# detectino.net
KiCad netlist of a schematic drawn in EAGLE
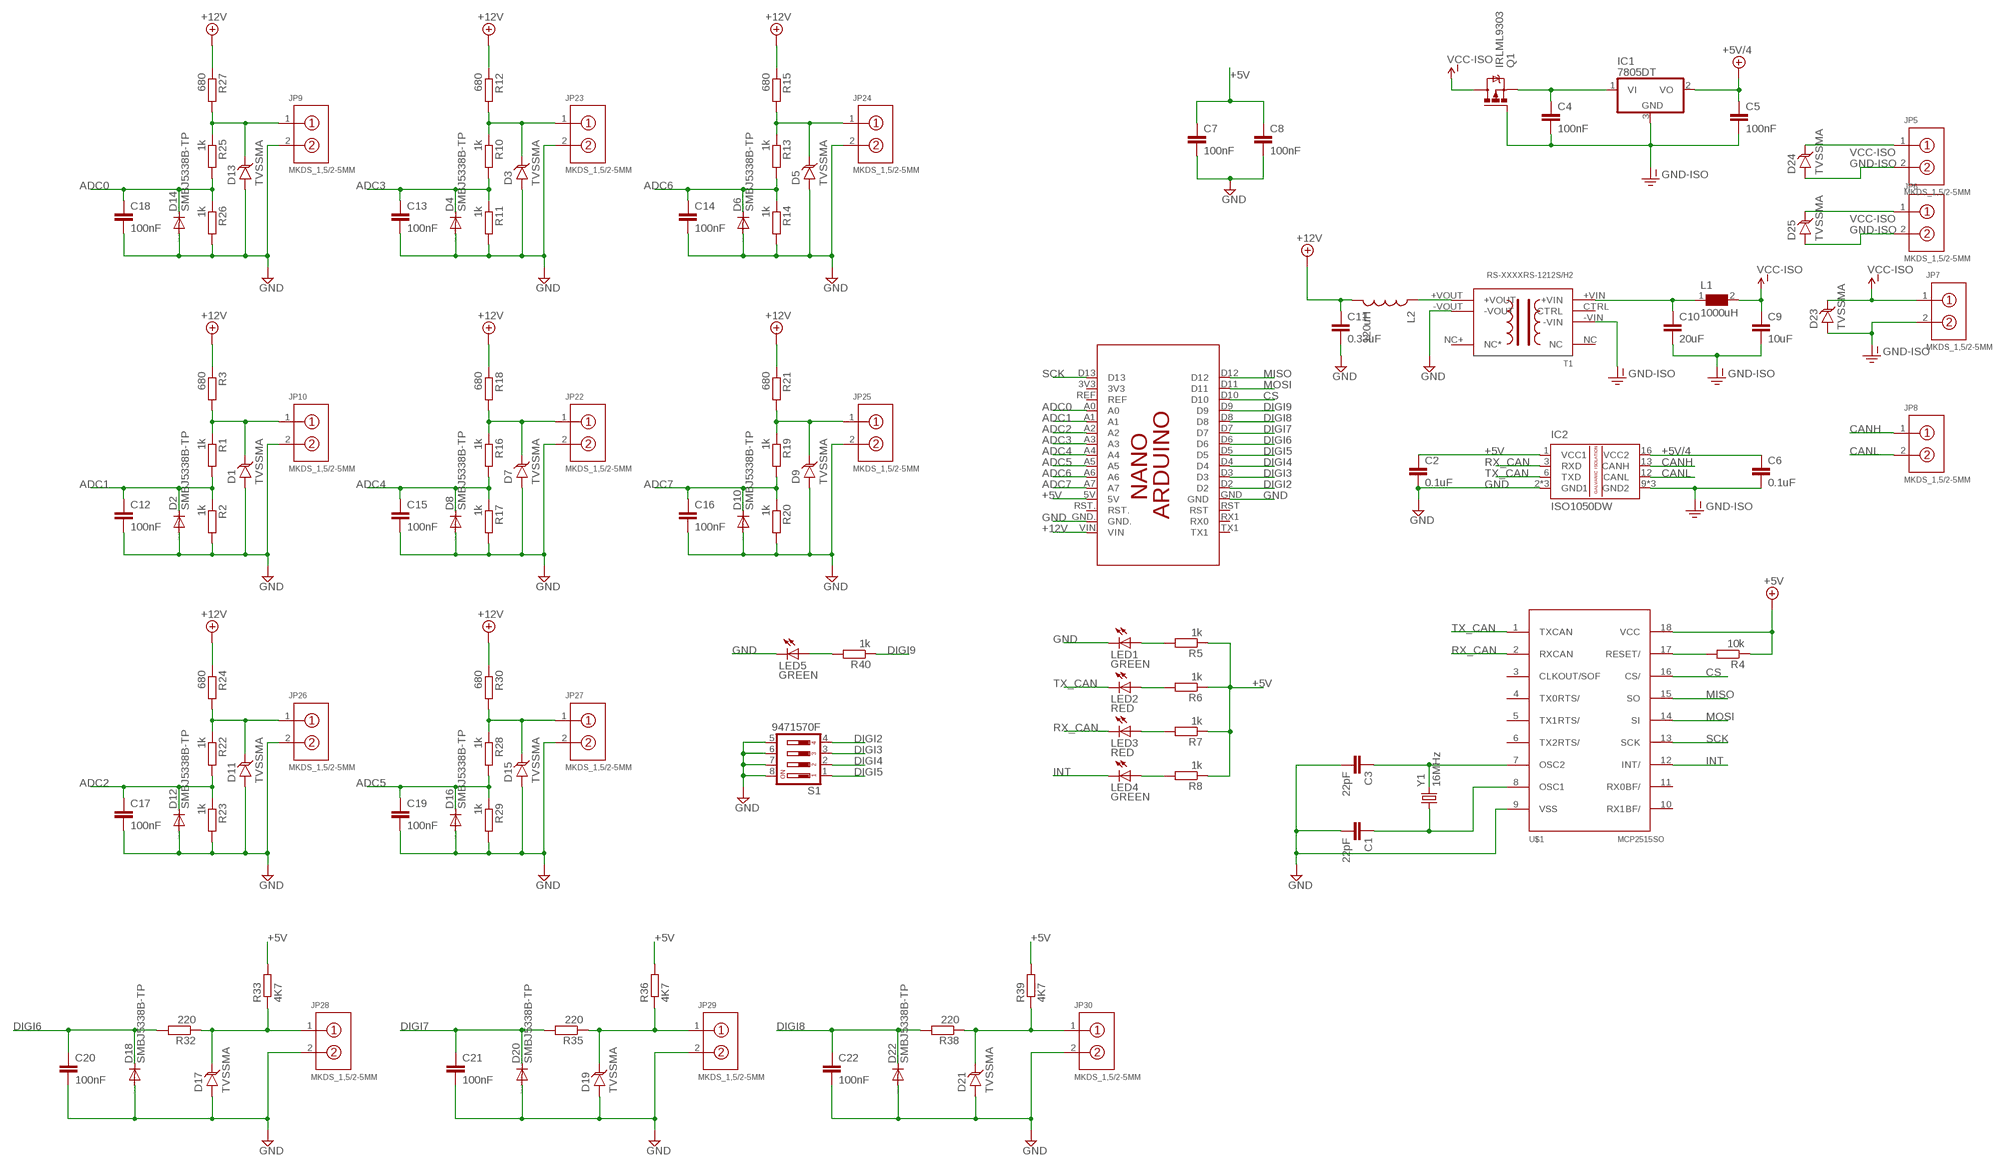
[diagram p0: schematic, sheet 1]

(export (version "E")
  (design (tool "Eeschema 10.0.6"))
  (components
    (comp (ref "C1")
      (value "22pF")
      (footprint "eagle-import:C1206K")
      (libsource (lib "eagle-import") (part "C-EUC1206K"))
    )
    (comp (ref "C2")
      (value "0.1uF")
      (footprint "eagle-import:C1206K")
      (libsource (lib "eagle-import") (part "C-EUC1206K"))
    )
    (comp (ref "C3")
      (value "22pF")
      (footprint "eagle-import:C1206K")
      (libsource (lib "eagle-import") (part "C-EUC1206K"))
    )
    (comp (ref "C4")
      (value "100nF")
      (footprint "eagle-import:C1206K")
      (libsource (lib "eagle-import") (part "C-EUC1206K"))
    )
    (comp (ref "C5")
      (value "100nF")
      (footprint "eagle-import:C1206K")
      (libsource (lib "eagle-import") (part "C-EUC1206K"))
    )
    (comp (ref "C6")
      (value "0.1uF")
      (footprint "eagle-import:C1206K")
      (libsource (lib "eagle-import") (part "C-EUC1206K"))
    )
    (comp (ref "C7")
      (value "100nF")
      (footprint "eagle-import:C1206K")
      (libsource (lib "eagle-import") (part "C-EUC1206K"))
    )
    (comp (ref "C8")
      (value "100nF")
      (footprint "eagle-import:C1206K")
      (libsource (lib "eagle-import") (part "C-EUC1206K"))
    )
    (comp (ref "C9")
      (value "10uF")
      (footprint "eagle-import:C1206K")
      (libsource (lib "eagle-import") (part "C-EUC1206K"))
    )
    (comp (ref "C10")
      (value "20uF")
      (footprint "eagle-import:C1206K")
      (libsource (lib "eagle-import") (part "C-EUC1206K"))
    )
    (comp (ref "C11")
      (value "0.33uF")
      (footprint "eagle-import:C1206K")
      (libsource (lib "eagle-import") (part "C-EUC1206K"))
    )
    (comp (ref "C12")
      (value "100nF")
      (footprint "eagle-import:C1206K")
      (libsource (lib "eagle-import") (part "C-EUC1206K"))
    )
    (comp (ref "C13")
      (value "100nF")
      (footprint "eagle-import:C0805K")
      (libsource (lib "eagle-import") (part "C-EUC0805K"))
    )
    (comp (ref "C14")
      (value "100nF")
      (footprint "eagle-import:C1206K")
      (libsource (lib "eagle-import") (part "C-EUC1206K"))
    )
    (comp (ref "C15")
      (value "100nF")
      (footprint "eagle-import:C1206K")
      (libsource (lib "eagle-import") (part "C-EUC1206K"))
    )
    (comp (ref "C16")
      (value "100nF")
      (footprint "eagle-import:C1206K")
      (libsource (lib "eagle-import") (part "C-EUC1206K"))
    )
    (comp (ref "C17")
      (value "100nF")
      (footprint "eagle-import:C1206K")
      (libsource (lib "eagle-import") (part "C-EUC1206K"))
    )
    (comp (ref "C18")
      (value "100nF")
      (footprint "eagle-import:C1206K")
      (libsource (lib "eagle-import") (part "C-EUC1206K"))
    )
    (comp (ref "C19")
      (value "100nF")
      (footprint "eagle-import:C0805K")
      (libsource (lib "eagle-import") (part "C-EUC0805K"))
    )
    (comp (ref "C20")
      (value "100nF")
      (footprint "eagle-import:C1206K")
      (libsource (lib "eagle-import") (part "C-EUC1206K"))
    )
    (comp (ref "C21")
      (value "100nF")
      (footprint "eagle-import:C1206K")
      (libsource (lib "eagle-import") (part "C-EUC1206K"))
    )
    (comp (ref "C22")
      (value "100nF")
      (footprint "eagle-import:C1206K")
      (libsource (lib "eagle-import") (part "C-EUC1206K"))
    )
    (comp (ref "D1")
      (value "TVSSMA")
      (footprint "eagle-import:SMA-DIODE")
      (libsource (lib "eagle-import") (part "TVSSMA"))
    )
    (comp (ref "D2")
      (value "SMBJ5338B-TP")
      (footprint "eagle-import:DO214AA")
      (libsource (lib "eagle-import") (part "DIODE-DO214AA"))
    )
    (comp (ref "D3")
      (value "TVSSMA")
      (footprint "eagle-import:SMA-DIODE")
      (libsource (lib "eagle-import") (part "TVSSMA"))
    )
    (comp (ref "D4")
      (value "SMBJ5338B-TP")
      (footprint "eagle-import:DO214AA")
      (libsource (lib "eagle-import") (part "DIODE-DO214AA"))
    )
    (comp (ref "D5")
      (value "TVSSMA")
      (footprint "eagle-import:SMA-DIODE")
      (libsource (lib "eagle-import") (part "TVSSMA"))
    )
    (comp (ref "D6")
      (value "SMBJ5338B-TP")
      (footprint "eagle-import:DO214AA")
      (libsource (lib "eagle-import") (part "DIODE-DO214AA"))
    )
    (comp (ref "D7")
      (value "TVSSMA")
      (footprint "eagle-import:SMA-DIODE")
      (libsource (lib "eagle-import") (part "TVSSMA"))
    )
    (comp (ref "D8")
      (value "SMBJ5338B-TP")
      (footprint "eagle-import:DO214AA")
      (libsource (lib "eagle-import") (part "DIODE-DO214AA"))
    )
    (comp (ref "D9")
      (value "TVSSMA")
      (footprint "eagle-import:SMA-DIODE")
      (libsource (lib "eagle-import") (part "TVSSMA"))
    )
    (comp (ref "D10")
      (value "SMBJ5338B-TP")
      (footprint "eagle-import:DO214AA")
      (libsource (lib "eagle-import") (part "DIODE-DO214AA"))
    )
    (comp (ref "D11")
      (value "TVSSMA")
      (footprint "eagle-import:SMA-DIODE")
      (libsource (lib "eagle-import") (part "TVSSMA"))
    )
    (comp (ref "D12")
      (value "SMBJ5338B-TP")
      (footprint "eagle-import:DO214AA")
      (libsource (lib "eagle-import") (part "DIODE-DO214AA"))
    )
    (comp (ref "D13")
      (value "TVSSMA")
      (footprint "eagle-import:SMA-DIODE")
      (libsource (lib "eagle-import") (part "TVSSMA"))
    )
    (comp (ref "D14")
      (value "SMBJ5338B-TP")
      (footprint "eagle-import:DO214AA")
      (libsource (lib "eagle-import") (part "DIODE-DO214AA"))
    )
    (comp (ref "D15")
      (value "TVSSMA")
      (footprint "eagle-import:SMA-DIODE")
      (libsource (lib "eagle-import") (part "TVSSMA"))
    )
    (comp (ref "D16")
      (value "SMBJ5338B-TP")
      (footprint "eagle-import:DO214AA")
      (libsource (lib "eagle-import") (part "DIODE-DO214AA"))
    )
    (comp (ref "D17")
      (value "TVSSMA")
      (footprint "eagle-import:SMA-DIODE")
      (libsource (lib "eagle-import") (part "TVSSMA"))
    )
    (comp (ref "D18")
      (value "SMBJ5338B-TP")
      (footprint "eagle-import:DO214AA")
      (libsource (lib "eagle-import") (part "DIODE-DO214AA"))
    )
    (comp (ref "D19")
      (value "TVSSMA")
      (footprint "eagle-import:SMA-DIODE")
      (libsource (lib "eagle-import") (part "TVSSMA"))
    )
    (comp (ref "D20")
      (value "SMBJ5338B-TP")
      (footprint "eagle-import:DO214AA")
      (libsource (lib "eagle-import") (part "DIODE-DO214AA"))
    )
    (comp (ref "D21")
      (value "TVSSMA")
      (footprint "eagle-import:SMA-DIODE")
      (libsource (lib "eagle-import") (part "TVSSMA"))
    )
    (comp (ref "D22")
      (value "SMBJ5338B-TP")
      (footprint "eagle-import:DO214AA")
      (libsource (lib "eagle-import") (part "DIODE-DO214AA"))
    )
    (comp (ref "D23")
      (value "TVSSMA")
      (footprint "eagle-import:SMA-DIODE")
      (libsource (lib "eagle-import") (part "TVSSMA"))
    )
    (comp (ref "D24")
      (value "TVSSMA")
      (footprint "eagle-import:SMA-DIODE")
      (libsource (lib "eagle-import") (part "TVSSMA"))
    )
    (comp (ref "D25")
      (value "TVSSMA")
      (footprint "eagle-import:SMA-DIODE")
      (libsource (lib "eagle-import") (part "TVSSMA"))
    )
    (comp (ref "IC1")
      (value "7805DT")
      (footprint "eagle-import:TO252")
      (libsource (lib "eagle-import") (part "78DT05"))
    )
    (comp (ref "IC2")
      (value "ISO1050DW")
      (footprint "eagle-import:SO-16DW")
      (libsource (lib "eagle-import") (part "ISO1050DW"))
    )
    (comp (ref "JP5")
      (value "MKDS_1,5/2-5MM")
      (footprint "eagle-import:MKDS_1,5_2-5MM")
      (libsource (lib "eagle-import") (part "MKDS_1,5/2-5MM"))
    )
    (comp (ref "JP6")
      (value "MKDS_1,5/2-5MM")
      (footprint "eagle-import:MKDS_1,5_2-5MM")
      (libsource (lib "eagle-import") (part "MKDS_1,5/2-5MM"))
    )
    (comp (ref "JP7")
      (value "MKDS_1,5/2-5MM")
      (footprint "eagle-import:MKDS_1,5_2-5MM")
      (libsource (lib "eagle-import") (part "MKDS_1,5/2-5MM"))
    )
    (comp (ref "JP8")
      (value "MKDS_1,5/2-5MM")
      (footprint "eagle-import:MKDS_1,5_2-5MM")
      (libsource (lib "eagle-import") (part "MKDS_1,5/2-5MM"))
    )
    (comp (ref "JP9")
      (value "MKDS_1,5/2-5MM")
      (footprint "eagle-import:MKDS_1,5_2-5MM")
      (libsource (lib "eagle-import") (part "MKDS_1,5/2-5MM"))
    )
    (comp (ref "JP10")
      (value "MKDS_1,5/2-5MM")
      (footprint "eagle-import:MKDS_1,5_2-5MM")
      (libsource (lib "eagle-import") (part "MKDS_1,5/2-5MM"))
    )
    (comp (ref "JP22")
      (value "MKDS_1,5/2-5MM")
      (footprint "eagle-import:MKDS_1,5_2-5MM")
      (libsource (lib "eagle-import") (part "MKDS_1,5/2-5MM"))
    )
    (comp (ref "JP23")
      (value "MKDS_1,5/2-5MM")
      (footprint "eagle-import:MKDS_1,5_2-5MM")
      (libsource (lib "eagle-import") (part "MKDS_1,5/2-5MM"))
    )
    (comp (ref "JP24")
      (value "MKDS_1,5/2-5MM")
      (footprint "eagle-import:MKDS_1,5_2-5MM")
      (libsource (lib "eagle-import") (part "MKDS_1,5/2-5MM"))
    )
    (comp (ref "JP25")
      (value "MKDS_1,5/2-5MM")
      (footprint "eagle-import:MKDS_1,5_2-5MM")
      (libsource (lib "eagle-import") (part "MKDS_1,5/2-5MM"))
    )
    (comp (ref "JP26")
      (value "MKDS_1,5/2-5MM")
      (footprint "eagle-import:MKDS_1,5_2-5MM")
      (libsource (lib "eagle-import") (part "MKDS_1,5/2-5MM"))
    )
    (comp (ref "JP27")
      (value "MKDS_1,5/2-5MM")
      (footprint "eagle-import:MKDS_1,5_2-5MM")
      (libsource (lib "eagle-import") (part "MKDS_1,5/2-5MM"))
    )
    (comp (ref "JP28")
      (value "MKDS_1,5/2-5MM")
      (footprint "eagle-import:MKDS_1,5_2-5MM")
      (libsource (lib "eagle-import") (part "MKDS_1,5/2-5MM"))
    )
    (comp (ref "JP29")
      (value "MKDS_1,5/2-5MM")
      (footprint "eagle-import:MKDS_1,5_2-5MM")
      (libsource (lib "eagle-import") (part "MKDS_1,5/2-5MM"))
    )
    (comp (ref "JP30")
      (value "MKDS_1,5/2-5MM")
      (footprint "eagle-import:MKDS_1,5_2-5MM")
      (libsource (lib "eagle-import") (part "MKDS_1,5/2-5MM"))
    )
    (comp (ref "L1")
      (value "1000uH")
      (footprint "eagle-import:WE-TIS_1111")
      (fields (field (name "MPN") "7447471102"))
      (libsource (lib "eagle-import") (part "WE-TIS_1111-7447471102"))
    )
    (comp (ref "L2")
      (value "120uH")
      (footprint "eagle-import:SDR0403")
      (libsource (lib "eagle-import") (part "INDUCTORSDR0403-560KL"))
    )
    (comp (ref "LED1")
      (value "GREEN")
      (footprint "eagle-import:SML1206")
      (libsource (lib "eagle-import") (part "LEDSML1206"))
    )
    (comp (ref "LED2")
      (value "RED")
      (footprint "eagle-import:SML1206")
      (libsource (lib "eagle-import") (part "LEDSML1206"))
    )
    (comp (ref "LED3")
      (value "RED")
      (footprint "eagle-import:SML1206")
      (libsource (lib "eagle-import") (part "LEDSML1206"))
    )
    (comp (ref "LED4")
      (value "GREEN")
      (footprint "eagle-import:SML1206")
      (libsource (lib "eagle-import") (part "LEDSML1206"))
    )
    (comp (ref "LED5")
      (value "GREEN")
      (footprint "eagle-import:SML1206")
      (libsource (lib "eagle-import") (part "LEDSML1206"))
    )
    (comp (ref "PCB2")
      (value "ARDUINO_NANO")
      (footprint "eagle-import:ARDUINO_NANO")
      (libsource (lib "eagle-import") (part "ARDUINO_NANO"))
    )
    (comp (ref "Q1")
      (value "IRLML9303")
      (footprint "eagle-import:MICRO3")
      (libsource (lib "eagle-import") (part "IRLML5203"))
    )
    (comp (ref "R1")
      (value "1k")
      (footprint "eagle-import:R1206")
      (libsource (lib "eagle-import") (part "R-EU_R1206"))
    )
    (comp (ref "R2")
      (value "1k")
      (footprint "eagle-import:R1206")
      (libsource (lib "eagle-import") (part "R-EU_R1206"))
    )
    (comp (ref "R3")
      (value "680")
      (footprint "eagle-import:R1206")
      (libsource (lib "eagle-import") (part "R-EU_R1206"))
    )
    (comp (ref "R4")
      (value "10k")
      (footprint "eagle-import:R1206")
      (libsource (lib "eagle-import") (part "R-EU_R1206"))
    )
    (comp (ref "R5")
      (value "1k")
      (footprint "eagle-import:R1206")
      (libsource (lib "eagle-import") (part "R-EU_R1206"))
    )
    (comp (ref "R6")
      (value "1k")
      (footprint "eagle-import:R1206")
      (libsource (lib "eagle-import") (part "R-EU_R1206"))
    )
    (comp (ref "R7")
      (value "1k")
      (footprint "eagle-import:R1206")
      (libsource (lib "eagle-import") (part "R-EU_R1206"))
    )
    (comp (ref "R8")
      (value "1k")
      (footprint "eagle-import:R1206")
      (libsource (lib "eagle-import") (part "R-EU_R1206"))
    )
    (comp (ref "R10")
      (value "1k")
      (footprint "eagle-import:R1206")
      (libsource (lib "eagle-import") (part "R-EU_R1206"))
    )
    (comp (ref "R11")
      (value "1k")
      (footprint "eagle-import:R1206")
      (libsource (lib "eagle-import") (part "R-EU_R1206"))
    )
    (comp (ref "R12")
      (value "680")
      (footprint "eagle-import:R1206")
      (libsource (lib "eagle-import") (part "R-EU_R1206"))
    )
    (comp (ref "R13")
      (value "1k")
      (footprint "eagle-import:R1206")
      (libsource (lib "eagle-import") (part "R-EU_R1206"))
    )
    (comp (ref "R14")
      (value "1k")
      (footprint "eagle-import:R1206")
      (libsource (lib "eagle-import") (part "R-EU_R1206"))
    )
    (comp (ref "R15")
      (value "680")
      (footprint "eagle-import:R1206")
      (libsource (lib "eagle-import") (part "R-EU_R1206"))
    )
    (comp (ref "R16")
      (value "1k")
      (footprint "eagle-import:R1206")
      (libsource (lib "eagle-import") (part "R-EU_R1206"))
    )
    (comp (ref "R17")
      (value "1k")
      (footprint "eagle-import:R1206")
      (libsource (lib "eagle-import") (part "R-EU_R1206"))
    )
    (comp (ref "R18")
      (value "680")
      (footprint "eagle-import:R1206")
      (libsource (lib "eagle-import") (part "R-EU_R1206"))
    )
    (comp (ref "R19")
      (value "1k")
      (footprint "eagle-import:R1206")
      (libsource (lib "eagle-import") (part "R-EU_R1206"))
    )
    (comp (ref "R20")
      (value "1k")
      (footprint "eagle-import:R1206")
      (libsource (lib "eagle-import") (part "R-EU_R1206"))
    )
    (comp (ref "R21")
      (value "680")
      (footprint "eagle-import:R1206")
      (libsource (lib "eagle-import") (part "R-EU_R1206"))
    )
    (comp (ref "R22")
      (value "1k")
      (footprint "eagle-import:R1206")
      (libsource (lib "eagle-import") (part "R-EU_R1206"))
    )
    (comp (ref "R23")
      (value "1k")
      (footprint "eagle-import:R1206")
      (libsource (lib "eagle-import") (part "R-EU_R1206"))
    )
    (comp (ref "R24")
      (value "680")
      (footprint "eagle-import:M1206")
      (libsource (lib "eagle-import") (part "R-EU_M1206"))
    )
    (comp (ref "R25")
      (value "1k")
      (footprint "eagle-import:R1206")
      (libsource (lib "eagle-import") (part "R-EU_R1206"))
    )
    (comp (ref "R26")
      (value "1k")
      (footprint "eagle-import:R1206")
      (libsource (lib "eagle-import") (part "R-EU_R1206"))
    )
    (comp (ref "R27")
      (value "680")
      (footprint "eagle-import:R1206")
      (libsource (lib "eagle-import") (part "R-EU_R1206"))
    )
    (comp (ref "R28")
      (value "1k")
      (footprint "eagle-import:R1206")
      (libsource (lib "eagle-import") (part "R-EU_R1206"))
    )
    (comp (ref "R29")
      (value "1k")
      (footprint "eagle-import:R1206")
      (libsource (lib "eagle-import") (part "R-EU_R1206"))
    )
    (comp (ref "R30")
      (value "680")
      (footprint "eagle-import:R1206")
      (libsource (lib "eagle-import") (part "R-EU_R1206"))
    )
    (comp (ref "R32")
      (value "220")
      (footprint "eagle-import:R1206")
      (libsource (lib "eagle-import") (part "R-EU_R1206"))
    )
    (comp (ref "R33")
      (value "4K7")
      (footprint "eagle-import:R1206")
      (libsource (lib "eagle-import") (part "R-EU_R1206"))
    )
    (comp (ref "R35")
      (value "220")
      (footprint "eagle-import:R1206")
      (libsource (lib "eagle-import") (part "R-EU_R1206"))
    )
    (comp (ref "R36")
      (value "4K7")
      (footprint "eagle-import:R1206")
      (libsource (lib "eagle-import") (part "R-EU_R1206"))
    )
    (comp (ref "R38")
      (value "220")
      (footprint "eagle-import:R1206")
      (libsource (lib "eagle-import") (part "R-EU_R1206"))
    )
    (comp (ref "R39")
      (value "4K7")
      (footprint "eagle-import:R1206")
      (libsource (lib "eagle-import") (part "R-EU_R1206"))
    )
    (comp (ref "R40")
      (value "1k")
      (footprint "eagle-import:R1206")
      (libsource (lib "eagle-import") (part "R-EU_R1206"))
    )
    (comp (ref "S1")
      (value "9471570F")
      (footprint "eagle-import:DS-04")
      (libsource (lib "eagle-import") (part "DS04"))
    )
    (comp (ref "T1")
      (value "RS-XXXXRS-1212S/H2")
      (footprint "eagle-import:SIP8")
      (libsource (lib "eagle-import") (part "RS-XXXXRS-1212S/H2"))
    )
    (comp (ref "U$1")
      (value "MCP2515SO")
      (footprint "eagle-import:SO18L")
      (libsource (lib "eagle-import") (part "MCP2515SO"))
    )
    (comp (ref "Y1")
      (value "16MHz")
      (footprint "eagle-import:HC49US")
      (libsource (lib "eagle-import") (part "CRYSTALHC49US"))
    )
  )
  (nets
    (net (code "1") (name "+5V") (class "Default")
      (node (ref "C2") (pin "1") (pinfunction "1_1") (pintype "passive"))
      (node (ref "C7") (pin "1") (pinfunction "1_1") (pintype "passive"))
      (node (ref "C8") (pin "1") (pinfunction "1_1") (pintype "passive"))
      (node (ref "IC2") (pin "1") (pinfunction "VCC1_1") (pintype "input"))
      (node (ref "PCB2") (pin "5V") (pinfunction "5V_5V") (pintype "bidirectional"))
      (node (ref "R33") (pin "2") (pinfunction "2_2") (pintype "passive"))
      (node (ref "R36") (pin "2") (pinfunction "2_2") (pintype "passive"))
      (node (ref "R39") (pin "2") (pinfunction "2_2") (pintype "passive"))
      (node (ref "R4") (pin "1") (pinfunction "1_1") (pintype "passive"))
      (node (ref "R5") (pin "1") (pinfunction "1_1") (pintype "passive"))
      (node (ref "R6") (pin "1") (pinfunction "1_1") (pintype "passive"))
      (node (ref "R7") (pin "1") (pinfunction "1_1") (pintype "passive"))
      (node (ref "R8") (pin "1") (pinfunction "1_1") (pintype "passive"))
      (node (ref "U$1") (pin "18") (pinfunction "VCC_18") (pintype "power_in"))
    )
    (net (code "2") (name "+5V{slash}4") (class "Default")
      (node (ref "C5") (pin "1") (pinfunction "1_1") (pintype "passive"))
      (node (ref "C6") (pin "1") (pinfunction "1_1") (pintype "passive"))
      (node (ref "IC1") (pin "2") (pinfunction "VO_2") (pintype "passive"))
      (node (ref "IC2") (pin "16") (pinfunction "VCC2_16") (pintype "input"))
    )
    (net (code "3") (name "+12V") (class "Default")
      (node (ref "C11") (pin "1") (pinfunction "1_1") (pintype "passive"))
      (node (ref "L2") (pin "P$2") (pinfunction "2_P$2") (pintype "passive"))
      (node (ref "PCB2") (pin "VIN") (pinfunction "VIN_VIN") (pintype "bidirectional"))
      (node (ref "R12") (pin "1") (pinfunction "1_1") (pintype "passive"))
      (node (ref "R15") (pin "1") (pinfunction "1_1") (pintype "passive"))
      (node (ref "R18") (pin "1") (pinfunction "1_1") (pintype "passive"))
      (node (ref "R21") (pin "1") (pinfunction "1_1") (pintype "passive"))
      (node (ref "R24") (pin "1") (pinfunction "1_1") (pintype "passive"))
      (node (ref "R27") (pin "1") (pinfunction "1_1") (pintype "passive"))
      (node (ref "R3") (pin "1") (pinfunction "1_1") (pintype "passive"))
      (node (ref "R30") (pin "1") (pinfunction "1_1") (pintype "passive"))
    )
    (net (code "4") (name "/ADC0") (class "Default")
      (node (ref "C18") (pin "1") (pinfunction "1_1") (pintype "passive"))
      (node (ref "D14") (pin "C") (pinfunction "C_C") (pintype "passive"))
      (node (ref "PCB2") (pin "A0") (pinfunction "A0_A0") (pintype "bidirectional"))
      (node (ref "R25") (pin "2") (pinfunction "2_2") (pintype "passive"))
      (node (ref "R26") (pin "1") (pinfunction "1_1") (pintype "passive"))
    )
    (net (code "5") (name "/ADC1") (class "Default")
      (node (ref "C12") (pin "1") (pinfunction "1_1") (pintype "passive"))
      (node (ref "D2") (pin "C") (pinfunction "C_C") (pintype "passive"))
      (node (ref "PCB2") (pin "A1") (pinfunction "A1_A1") (pintype "bidirectional"))
      (node (ref "R1") (pin "2") (pinfunction "2_2") (pintype "passive"))
      (node (ref "R2") (pin "1") (pinfunction "1_1") (pintype "passive"))
    )
    (net (code "6") (name "/ADC2") (class "Default")
      (node (ref "C17") (pin "1") (pinfunction "1_1") (pintype "passive"))
      (node (ref "D12") (pin "C") (pinfunction "C_C") (pintype "passive"))
      (node (ref "PCB2") (pin "A2") (pinfunction "A2_A2") (pintype "bidirectional"))
      (node (ref "R22") (pin "2") (pinfunction "2_2") (pintype "passive"))
      (node (ref "R23") (pin "1") (pinfunction "1_1") (pintype "passive"))
    )
    (net (code "7") (name "/ADC3") (class "Default")
      (node (ref "C13") (pin "1") (pinfunction "1_1") (pintype "passive"))
      (node (ref "D4") (pin "C") (pinfunction "C_C") (pintype "passive"))
      (node (ref "PCB2") (pin "A3") (pinfunction "A3_A3") (pintype "bidirectional"))
      (node (ref "R10") (pin "2") (pinfunction "2_2") (pintype "passive"))
      (node (ref "R11") (pin "1") (pinfunction "1_1") (pintype "passive"))
    )
    (net (code "8") (name "/ADC4") (class "Default")
      (node (ref "C15") (pin "1") (pinfunction "1_1") (pintype "passive"))
      (node (ref "D8") (pin "C") (pinfunction "C_C") (pintype "passive"))
      (node (ref "PCB2") (pin "A4") (pinfunction "A4_A4") (pintype "bidirectional"))
      (node (ref "R16") (pin "2") (pinfunction "2_2") (pintype "passive"))
      (node (ref "R17") (pin "1") (pinfunction "1_1") (pintype "passive"))
    )
    (net (code "9") (name "/ADC5") (class "Default")
      (node (ref "C19") (pin "1") (pinfunction "1_1") (pintype "passive"))
      (node (ref "D16") (pin "C") (pinfunction "C_C") (pintype "passive"))
      (node (ref "PCB2") (pin "A5") (pinfunction "A5_A5") (pintype "bidirectional"))
      (node (ref "R28") (pin "2") (pinfunction "2_2") (pintype "passive"))
      (node (ref "R29") (pin "1") (pinfunction "1_1") (pintype "passive"))
    )
    (net (code "10") (name "/ADC6") (class "Default")
      (node (ref "C14") (pin "1") (pinfunction "1_1") (pintype "passive"))
      (node (ref "D6") (pin "C") (pinfunction "C_C") (pintype "passive"))
      (node (ref "PCB2") (pin "A6") (pinfunction "A6_A6") (pintype "bidirectional"))
      (node (ref "R13") (pin "2") (pinfunction "2_2") (pintype "passive"))
      (node (ref "R14") (pin "1") (pinfunction "1_1") (pintype "passive"))
    )
    (net (code "11") (name "/ADC7") (class "Default")
      (node (ref "C16") (pin "1") (pinfunction "1_1") (pintype "passive"))
      (node (ref "D10") (pin "C") (pinfunction "C_C") (pintype "passive"))
      (node (ref "PCB2") (pin "A7") (pinfunction "A7_A7") (pintype "bidirectional"))
      (node (ref "R19") (pin "2") (pinfunction "2_2") (pintype "passive"))
      (node (ref "R20") (pin "1") (pinfunction "1_1") (pintype "passive"))
    )
    (net (code "12") (name "/CANH") (class "Default")
      (node (ref "IC2") (pin "13") (pinfunction "CANH_13") (pintype "input"))
      (node (ref "JP8") (pin "1") (pinfunction "P$1_1") (pintype "bidirectional"))
    )
    (net (code "13") (name "/CANL") (class "Default")
      (node (ref "IC2") (pin "12") (pinfunction "CANL_12") (pintype "input"))
      (node (ref "JP8") (pin "2") (pinfunction "P$2_2") (pintype "bidirectional"))
    )
    (net (code "14") (name "/CS") (class "Default")
      (node (ref "PCB2") (pin "D10") (pinfunction "D10_D10") (pintype "bidirectional"))
      (node (ref "U$1") (pin "16") (pinfunction "CS/_16") (pintype "input"))
    )
    (net (code "15") (name "/DIGI2") (class "Default")
      (node (ref "PCB2") (pin "D2") (pinfunction "D2_D2") (pintype "bidirectional"))
      (node (ref "S1") (pin "4") (pinfunction "4_4") (pintype "passive"))
    )
    (net (code "16") (name "/DIGI3") (class "Default")
      (node (ref "PCB2") (pin "D3") (pinfunction "D3_D3") (pintype "bidirectional"))
      (node (ref "S1") (pin "3") (pinfunction "3_3") (pintype "passive"))
    )
    (net (code "17") (name "/DIGI4") (class "Default")
      (node (ref "PCB2") (pin "D4") (pinfunction "D4_D4") (pintype "bidirectional"))
      (node (ref "S1") (pin "2") (pinfunction "2_2") (pintype "passive"))
    )
    (net (code "18") (name "/DIGI5") (class "Default")
      (node (ref "PCB2") (pin "D5") (pinfunction "D5_D5") (pintype "bidirectional"))
      (node (ref "S1") (pin "1") (pinfunction "1_1") (pintype "passive"))
    )
    (net (code "19") (name "/DIGI6") (class "Default")
      (node (ref "C20") (pin "1") (pinfunction "1_1") (pintype "passive"))
      (node (ref "D18") (pin "C") (pinfunction "C_C") (pintype "passive"))
      (node (ref "PCB2") (pin "D6") (pinfunction "D6_D6") (pintype "bidirectional"))
      (node (ref "R32") (pin "2") (pinfunction "2_2") (pintype "passive"))
    )
    (net (code "20") (name "/DIGI7") (class "Default")
      (node (ref "C21") (pin "1") (pinfunction "1_1") (pintype "passive"))
      (node (ref "D20") (pin "C") (pinfunction "C_C") (pintype "passive"))
      (node (ref "PCB2") (pin "D7") (pinfunction "D7_D7") (pintype "bidirectional"))
      (node (ref "R35") (pin "2") (pinfunction "2_2") (pintype "passive"))
    )
    (net (code "21") (name "/DIGI8") (class "Default")
      (node (ref "C22") (pin "1") (pinfunction "1_1") (pintype "passive"))
      (node (ref "D22") (pin "C") (pinfunction "C_C") (pintype "passive"))
      (node (ref "PCB2") (pin "D8") (pinfunction "D8_D8") (pintype "bidirectional"))
      (node (ref "R38") (pin "2") (pinfunction "2_2") (pintype "passive"))
    )
    (net (code "22") (name "/DIGI9") (class "Default")
      (node (ref "PCB2") (pin "D9") (pinfunction "D9_D9") (pintype "bidirectional"))
      (node (ref "R40") (pin "1") (pinfunction "1_1") (pintype "passive"))
    )
    (net (code "23") (name "/INT") (class "Default")
      (node (ref "LED4") (pin "C") (pinfunction "C_C") (pintype "passive"))
      (node (ref "U$1") (pin "12") (pinfunction "INT/_12") (pintype "output"))
    )
    (net (code "24") (name "/MISO") (class "Default")
      (node (ref "PCB2") (pin "D12") (pinfunction "D12_D12") (pintype "bidirectional"))
      (node (ref "U$1") (pin "15") (pinfunction "SO_15") (pintype "output"))
    )
    (net (code "25") (name "/MOSI") (class "Default")
      (node (ref "PCB2") (pin "D11") (pinfunction "D11_D11") (pintype "bidirectional"))
      (node (ref "U$1") (pin "14") (pinfunction "SI_14") (pintype "input"))
    )
    (net (code "26") (name "/RX_CAN") (class "Default")
      (node (ref "IC2") (pin "3") (pinfunction "RXD_3") (pintype "input"))
      (node (ref "LED3") (pin "C") (pinfunction "C_C") (pintype "passive"))
      (node (ref "U$1") (pin "2") (pinfunction "RXCAN_2") (pintype "input"))
    )
    (net (code "27") (name "/SCK") (class "Default")
      (node (ref "PCB2") (pin "D13") (pinfunction "D13_D13") (pintype "bidirectional"))
      (node (ref "U$1") (pin "13") (pinfunction "SCK_13") (pintype "input"))
    )
    (net (code "28") (name "/TX_CAN") (class "Default")
      (node (ref "IC2") (pin "6") (pinfunction "TXD_6") (pintype "input"))
      (node (ref "LED2") (pin "C") (pinfunction "C_C") (pintype "passive"))
      (node (ref "U$1") (pin "1") (pinfunction "TXCAN_1") (pintype "output"))
    )
    (net (code "29") (name "GND") (class "Default")
      (node (ref "C1") (pin "2") (pinfunction "2_2") (pintype "passive"))
      (node (ref "C11") (pin "2") (pinfunction "2_2") (pintype "passive"))
      (node (ref "C12") (pin "2") (pinfunction "2_2") (pintype "passive"))
      (node (ref "C13") (pin "2") (pinfunction "2_2") (pintype "passive"))
      (node (ref "C14") (pin "2") (pinfunction "2_2") (pintype "passive"))
      (node (ref "C15") (pin "2") (pinfunction "2_2") (pintype "passive"))
      (node (ref "C16") (pin "2") (pinfunction "2_2") (pintype "passive"))
      (node (ref "C17") (pin "2") (pinfunction "2_2") (pintype "passive"))
      (node (ref "C18") (pin "2") (pinfunction "2_2") (pintype "passive"))
      (node (ref "C19") (pin "2") (pinfunction "2_2") (pintype "passive"))
      (node (ref "C2") (pin "2") (pinfunction "2_2") (pintype "passive"))
      (node (ref "C20") (pin "2") (pinfunction "2_2") (pintype "passive"))
      (node (ref "C21") (pin "2") (pinfunction "2_2") (pintype "passive"))
      (node (ref "C22") (pin "2") (pinfunction "2_2") (pintype "passive"))
      (node (ref "C3") (pin "2") (pinfunction "2_2") (pintype "passive"))
      (node (ref "C7") (pin "2") (pinfunction "2_2") (pintype "passive"))
      (node (ref "C8") (pin "2") (pinfunction "2_2") (pintype "passive"))
      (node (ref "D1") (pin "A") (pinfunction "A_A") (pintype "passive"))
      (node (ref "D10") (pin "A") (pinfunction "A_A") (pintype "passive"))
      (node (ref "D11") (pin "A") (pinfunction "A_A") (pintype "passive"))
      (node (ref "D12") (pin "A") (pinfunction "A_A") (pintype "passive"))
      (node (ref "D13") (pin "A") (pinfunction "A_A") (pintype "passive"))
      (node (ref "D14") (pin "A") (pinfunction "A_A") (pintype "passive"))
      (node (ref "D15") (pin "A") (pinfunction "A_A") (pintype "passive"))
      (node (ref "D16") (pin "A") (pinfunction "A_A") (pintype "passive"))
      (node (ref "D17") (pin "A") (pinfunction "A_A") (pintype "passive"))
      (node (ref "D18") (pin "A") (pinfunction "A_A") (pintype "passive"))
      (node (ref "D19") (pin "A") (pinfunction "A_A") (pintype "passive"))
      (node (ref "D2") (pin "A") (pinfunction "A_A") (pintype "passive"))
      (node (ref "D20") (pin "A") (pinfunction "A_A") (pintype "passive"))
      (node (ref "D21") (pin "A") (pinfunction "A_A") (pintype "passive"))
      (node (ref "D22") (pin "A") (pinfunction "A_A") (pintype "passive"))
      (node (ref "D3") (pin "A") (pinfunction "A_A") (pintype "passive"))
      (node (ref "D4") (pin "A") (pinfunction "A_A") (pintype "passive"))
      (node (ref "D5") (pin "A") (pinfunction "A_A") (pintype "passive"))
      (node (ref "D6") (pin "A") (pinfunction "A_A") (pintype "passive"))
      (node (ref "D7") (pin "A") (pinfunction "A_A") (pintype "passive"))
      (node (ref "D8") (pin "A") (pinfunction "A_A") (pintype "passive"))
      (node (ref "D9") (pin "A") (pinfunction "A_A") (pintype "passive"))
      (node (ref "IC2") (pin "2") (pinfunction "GND1_2") (pintype "input"))
      (node (ref "IC2") (pin "7") (pinfunction "GND1_7") (pintype "input"))
      (node (ref "IC2") (pin "8") (pinfunction "GND1_8") (pintype "input"))
      (node (ref "JP10") (pin "2") (pinfunction "P$2_2") (pintype "bidirectional"))
      (node (ref "JP22") (pin "2") (pinfunction "P$2_2") (pintype "bidirectional"))
      (node (ref "JP23") (pin "2") (pinfunction "P$2_2") (pintype "bidirectional"))
      (node (ref "JP24") (pin "2") (pinfunction "P$2_2") (pintype "bidirectional"))
      (node (ref "JP25") (pin "2") (pinfunction "P$2_2") (pintype "bidirectional"))
      (node (ref "JP26") (pin "2") (pinfunction "P$2_2") (pintype "bidirectional"))
      (node (ref "JP27") (pin "2") (pinfunction "P$2_2") (pintype "bidirectional"))
      (node (ref "JP28") (pin "2") (pinfunction "P$2_2") (pintype "bidirectional"))
      (node (ref "JP29") (pin "2") (pinfunction "P$2_2") (pintype "bidirectional"))
      (node (ref "JP30") (pin "2") (pinfunction "P$2_2") (pintype "bidirectional"))
      (node (ref "JP9") (pin "2") (pinfunction "P$2_2") (pintype "bidirectional"))
      (node (ref "LED1") (pin "C") (pinfunction "C_C") (pintype "passive"))
      (node (ref "LED5") (pin "C") (pinfunction "C_C") (pintype "passive"))
      (node (ref "PCB2") (pin "GND") (pinfunction "GND_GND") (pintype "bidirectional"))
      (node (ref "PCB2") (pin "GND.") (pinfunction "GND._GND.") (pintype "bidirectional"))
      (node (ref "R11") (pin "2") (pinfunction "2_2") (pintype "passive"))
      (node (ref "R14") (pin "2") (pinfunction "2_2") (pintype "passive"))
      (node (ref "R17") (pin "2") (pinfunction "2_2") (pintype "passive"))
      (node (ref "R2") (pin "2") (pinfunction "2_2") (pintype "passive"))
      (node (ref "R20") (pin "2") (pinfunction "2_2") (pintype "passive"))
      (node (ref "R23") (pin "2") (pinfunction "2_2") (pintype "passive"))
      (node (ref "R26") (pin "2") (pinfunction "2_2") (pintype "passive"))
      (node (ref "R29") (pin "2") (pinfunction "2_2") (pintype "passive"))
      (node (ref "S1") (pin "5") (pinfunction "5_5") (pintype "passive"))
      (node (ref "S1") (pin "6") (pinfunction "6_6") (pintype "passive"))
      (node (ref "S1") (pin "7") (pinfunction "7_7") (pintype "passive"))
      (node (ref "S1") (pin "8") (pinfunction "8_8") (pintype "passive"))
      (node (ref "T1") (pin "-VOUT") (pinfunction "-VOUT_-VOUT") (pintype "bidirectional"))
      (node (ref "U$1") (pin "9") (pinfunction "VSS_9") (pintype "power_in"))
    )
    (net (code "30") (name "GND-ISO") (class "Default")
      (node (ref "C10") (pin "2") (pinfunction "2_2") (pintype "passive"))
      (node (ref "C4") (pin "2") (pinfunction "2_2") (pintype "passive"))
      (node (ref "C5") (pin "2") (pinfunction "2_2") (pintype "passive"))
      (node (ref "C6") (pin "2") (pinfunction "2_2") (pintype "passive"))
      (node (ref "C9") (pin "2") (pinfunction "2_2") (pintype "passive"))
      (node (ref "D23") (pin "A") (pinfunction "A_A") (pintype "passive"))
      (node (ref "D24") (pin "A") (pinfunction "A_A") (pintype "passive"))
      (node (ref "D25") (pin "A") (pinfunction "A_A") (pintype "passive"))
      (node (ref "IC1") (pin "3") (pinfunction "GND_3") (pintype "passive"))
      (node (ref "IC2") (pin "10") (pinfunction "GND2_10") (pintype "input"))
      (node (ref "IC2") (pin "15") (pinfunction "GND2_15") (pintype "input"))
      (node (ref "IC2") (pin "9") (pinfunction "GND2_9") (pintype "input"))
      (node (ref "JP5") (pin "2") (pinfunction "P$2_2") (pintype "bidirectional"))
      (node (ref "JP6") (pin "2") (pinfunction "P$2_2") (pintype "bidirectional"))
      (node (ref "JP7") (pin "2") (pinfunction "P$2_2") (pintype "bidirectional"))
      (node (ref "Q1") (pin "1") (pinfunction "G_1") (pintype "passive"))
      (node (ref "T1") (pin "-VIN") (pinfunction "-VIN_-VIN") (pintype "bidirectional"))
    )
    (net (code "31") (name "Net-(C10-Pad1)") (class "Default")
      (node (ref "C10") (pin "1") (pinfunction "1_1") (pintype "passive"))
      (node (ref "L1") (pin "1") (pinfunction "1_1") (pintype "passive"))
      (node (ref "T1") (pin "+VIN") (pinfunction "+VIN_+VIN") (pintype "bidirectional"))
    )
    (net (code "32") (name "Net-(IC1-VI)") (class "Default")
      (node (ref "C4") (pin "1") (pinfunction "1_1") (pintype "passive"))
      (node (ref "IC1") (pin "1") (pinfunction "VI_1") (pintype "input"))
      (node (ref "Q1") (pin "2") (pinfunction "S_2") (pintype "passive"))
    )
    (net (code "33") (name "Net-(JP9-P$1)") (class "Default")
      (node (ref "D13") (pin "C") (pinfunction "C_C") (pintype "passive"))
      (node (ref "JP9") (pin "1") (pinfunction "P$1_1") (pintype "bidirectional"))
      (node (ref "R25") (pin "1") (pinfunction "1_1") (pintype "passive"))
      (node (ref "R27") (pin "2") (pinfunction "2_2") (pintype "passive"))
    )
    (net (code "34") (name "Net-(JP10-P$1)") (class "Default")
      (node (ref "D1") (pin "C") (pinfunction "C_C") (pintype "passive"))
      (node (ref "JP10") (pin "1") (pinfunction "P$1_1") (pintype "bidirectional"))
      (node (ref "R1") (pin "1") (pinfunction "1_1") (pintype "passive"))
      (node (ref "R3") (pin "2") (pinfunction "2_2") (pintype "passive"))
    )
    (net (code "35") (name "Net-(JP22-P$1)") (class "Default")
      (node (ref "D7") (pin "C") (pinfunction "C_C") (pintype "passive"))
      (node (ref "JP22") (pin "1") (pinfunction "P$1_1") (pintype "bidirectional"))
      (node (ref "R16") (pin "1") (pinfunction "1_1") (pintype "passive"))
      (node (ref "R18") (pin "2") (pinfunction "2_2") (pintype "passive"))
    )
    (net (code "36") (name "Net-(JP23-P$1)") (class "Default")
      (node (ref "D3") (pin "C") (pinfunction "C_C") (pintype "passive"))
      (node (ref "JP23") (pin "1") (pinfunction "P$1_1") (pintype "bidirectional"))
      (node (ref "R10") (pin "1") (pinfunction "1_1") (pintype "passive"))
      (node (ref "R12") (pin "2") (pinfunction "2_2") (pintype "passive"))
    )
    (net (code "37") (name "Net-(JP24-P$1)") (class "Default")
      (node (ref "D5") (pin "C") (pinfunction "C_C") (pintype "passive"))
      (node (ref "JP24") (pin "1") (pinfunction "P$1_1") (pintype "bidirectional"))
      (node (ref "R13") (pin "1") (pinfunction "1_1") (pintype "passive"))
      (node (ref "R15") (pin "2") (pinfunction "2_2") (pintype "passive"))
    )
    (net (code "38") (name "Net-(JP25-P$1)") (class "Default")
      (node (ref "D9") (pin "C") (pinfunction "C_C") (pintype "passive"))
      (node (ref "JP25") (pin "1") (pinfunction "P$1_1") (pintype "bidirectional"))
      (node (ref "R19") (pin "1") (pinfunction "1_1") (pintype "passive"))
      (node (ref "R21") (pin "2") (pinfunction "2_2") (pintype "passive"))
    )
    (net (code "39") (name "Net-(JP26-P$1)") (class "Default")
      (node (ref "D11") (pin "C") (pinfunction "C_C") (pintype "passive"))
      (node (ref "JP26") (pin "1") (pinfunction "P$1_1") (pintype "bidirectional"))
      (node (ref "R22") (pin "1") (pinfunction "1_1") (pintype "passive"))
      (node (ref "R24") (pin "2") (pinfunction "2_2") (pintype "passive"))
    )
    (net (code "40") (name "Net-(JP27-P$1)") (class "Default")
      (node (ref "D15") (pin "C") (pinfunction "C_C") (pintype "passive"))
      (node (ref "JP27") (pin "1") (pinfunction "P$1_1") (pintype "bidirectional"))
      (node (ref "R28") (pin "1") (pinfunction "1_1") (pintype "passive"))
      (node (ref "R30") (pin "2") (pinfunction "2_2") (pintype "passive"))
    )
    (net (code "41") (name "Net-(JP28-P$1)") (class "Default")
      (node (ref "D17") (pin "C") (pinfunction "C_C") (pintype "passive"))
      (node (ref "JP28") (pin "1") (pinfunction "P$1_1") (pintype "bidirectional"))
      (node (ref "R32") (pin "1") (pinfunction "1_1") (pintype "passive"))
      (node (ref "R33") (pin "1") (pinfunction "1_1") (pintype "passive"))
    )
    (net (code "42") (name "Net-(JP29-P$1)") (class "Default")
      (node (ref "D19") (pin "C") (pinfunction "C_C") (pintype "passive"))
      (node (ref "JP29") (pin "1") (pinfunction "P$1_1") (pintype "bidirectional"))
      (node (ref "R35") (pin "1") (pinfunction "1_1") (pintype "passive"))
      (node (ref "R36") (pin "1") (pinfunction "1_1") (pintype "passive"))
    )
    (net (code "43") (name "Net-(JP30-P$1)") (class "Default")
      (node (ref "D21") (pin "C") (pinfunction "C_C") (pintype "passive"))
      (node (ref "JP30") (pin "1") (pinfunction "P$1_1") (pintype "bidirectional"))
      (node (ref "R38") (pin "1") (pinfunction "1_1") (pintype "passive"))
      (node (ref "R39") (pin "1") (pinfunction "1_1") (pintype "passive"))
    )
    (net (code "44") (name "Net-(L2-1)") (class "Default")
      (node (ref "L2") (pin "P$1") (pinfunction "1_P$1") (pintype "passive"))
      (node (ref "T1") (pin "+VOUT") (pinfunction "+VOUT_+VOUT") (pintype "bidirectional"))
    )
    (net (code "45") (name "Net-(LED1-PadA)") (class "Default")
      (node (ref "LED1") (pin "A") (pinfunction "A_A") (pintype "passive"))
      (node (ref "R5") (pin "2") (pinfunction "2_2") (pintype "passive"))
    )
    (net (code "46") (name "Net-(LED2-PadA)") (class "Default")
      (node (ref "LED2") (pin "A") (pinfunction "A_A") (pintype "passive"))
      (node (ref "R6") (pin "2") (pinfunction "2_2") (pintype "passive"))
    )
    (net (code "47") (name "Net-(LED3-PadA)") (class "Default")
      (node (ref "LED3") (pin "A") (pinfunction "A_A") (pintype "passive"))
      (node (ref "R7") (pin "2") (pinfunction "2_2") (pintype "passive"))
    )
    (net (code "48") (name "Net-(LED4-PadA)") (class "Default")
      (node (ref "LED4") (pin "A") (pinfunction "A_A") (pintype "passive"))
      (node (ref "R8") (pin "2") (pinfunction "2_2") (pintype "passive"))
    )
    (net (code "49") (name "Net-(LED5-PadA)") (class "Default")
      (node (ref "LED5") (pin "A") (pinfunction "A_A") (pintype "passive"))
      (node (ref "R40") (pin "2") (pinfunction "2_2") (pintype "passive"))
    )
    (net (code "50") (name "Net-(U$1-OSC1)") (class "Default")
      (node (ref "C1") (pin "1") (pinfunction "1_1") (pintype "passive"))
      (node (ref "U$1") (pin "8") (pinfunction "OSC1_8") (pintype "bidirectional"))
      (node (ref "Y1") (pin "1") (pinfunction "1_1") (pintype "passive"))
    )
    (net (code "51") (name "Net-(U$1-OSC2)") (class "Default")
      (node (ref "C3") (pin "1") (pinfunction "1_1") (pintype "passive"))
      (node (ref "U$1") (pin "7") (pinfunction "OSC2_7") (pintype "bidirectional"))
      (node (ref "Y1") (pin "2") (pinfunction "2_2") (pintype "passive"))
    )
    (net (code "52") (name "Net-(U$1-RESET{slash})") (class "Default")
      (node (ref "R4") (pin "2") (pinfunction "2_2") (pintype "passive"))
      (node (ref "U$1") (pin "17") (pinfunction "RESET/_17") (pintype "input"))
    )
    (net (code "53") (name "VCC-ISO") (class "Default")
      (node (ref "C9") (pin "1") (pinfunction "1_1") (pintype "passive"))
      (node (ref "D23") (pin "C") (pinfunction "C_C") (pintype "passive"))
      (node (ref "D24") (pin "C") (pinfunction "C_C") (pintype "passive"))
      (node (ref "D25") (pin "C") (pinfunction "C_C") (pintype "passive"))
      (node (ref "JP5") (pin "1") (pinfunction "P$1_1") (pintype "bidirectional"))
      (node (ref "JP6") (pin "1") (pinfunction "P$1_1") (pintype "bidirectional"))
      (node (ref "JP7") (pin "1") (pinfunction "P$1_1") (pintype "bidirectional"))
      (node (ref "L1") (pin "2") (pinfunction "2_2") (pintype "passive"))
      (node (ref "Q1") (pin "3") (pinfunction "D_3") (pintype "passive"))
    )
    (net (code "54") (name "unconnected-(PCB2-Pad3V3)") (class "Default")
      (node (ref "PCB2") (pin "3V3") (pinfunction "3V3_3V3") (pintype "bidirectional"))
    )
    (net (code "55") (name "unconnected-(PCB2-PadREF)") (class "Default")
      (node (ref "PCB2") (pin "REF") (pinfunction "REF_REF") (pintype "bidirectional"))
    )
    (net (code "56") (name "unconnected-(PCB2-PadRST)") (class "Default")
      (node (ref "PCB2") (pin "RST") (pinfunction "RST_RST") (pintype "bidirectional"))
    )
    (net (code "57") (name "unconnected-(PCB2-PadRST.)") (class "Default")
      (node (ref "PCB2") (pin "RST.") (pinfunction "RST._RST.") (pintype "bidirectional"))
    )
    (net (code "58") (name "unconnected-(PCB2-PadTX1)") (class "Default")
      (node (ref "PCB2") (pin "TX1") (pinfunction "TX1_TX1") (pintype "bidirectional"))
    )
    (net (code "59") (name "unconnected-(PCB2-RX0-PadRX1)") (class "Default")
      (node (ref "PCB2") (pin "RX1") (pinfunction "RX0_RX1") (pintype "bidirectional"))
    )
    (net (code "60") (name "unconnected-(T1-NC*-PadNC+)") (class "Default")
      (node (ref "T1") (pin "NC+") (pinfunction "NC*_NC+") (pintype "bidirectional"))
    )
    (net (code "61") (name "unconnected-(T1-PadCTRL)") (class "Default")
      (node (ref "T1") (pin "CTRL") (pinfunction "CTRL_CTRL") (pintype "bidirectional"))
    )
    (net (code "62") (name "unconnected-(T1-PadNC)") (class "Default")
      (node (ref "T1") (pin "NC") (pinfunction "NC_NC") (pintype "bidirectional"))
    )
    (net (code "63") (name "unconnected-(U$1-CLKOUT{slash}SOF-Pad3)") (class "Default")
      (node (ref "U$1") (pin "3") (pinfunction "CLKOUT/SOF_3") (pintype "bidirectional"))
    )
    (net (code "64") (name "unconnected-(U$1-RX0BF{slash}-Pad11)") (class "Default")
      (node (ref "U$1") (pin "11") (pinfunction "RX0BF/_11") (pintype "bidirectional"))
    )
    (net (code "65") (name "unconnected-(U$1-RX1BF{slash}-Pad10)") (class "Default")
      (node (ref "U$1") (pin "10") (pinfunction "RX1BF/_10") (pintype "bidirectional"))
    )
    (net (code "66") (name "unconnected-(U$1-TX0RTS{slash}-Pad4)") (class "Default")
      (node (ref "U$1") (pin "4") (pinfunction "TX0RTS/_4") (pintype "bidirectional"))
    )
    (net (code "67") (name "unconnected-(U$1-TX1RTS{slash}-Pad5)") (class "Default")
      (node (ref "U$1") (pin "5") (pinfunction "TX1RTS/_5") (pintype "bidirectional"))
    )
    (net (code "68") (name "unconnected-(U$1-TX2RTS{slash}-Pad6)") (class "Default")
      (node (ref "U$1") (pin "6") (pinfunction "TX2RTS/_6") (pintype "bidirectional"))
    )
  )
)
